# Boden.net
KiCad netlist of a schematic drawn in EAGLE
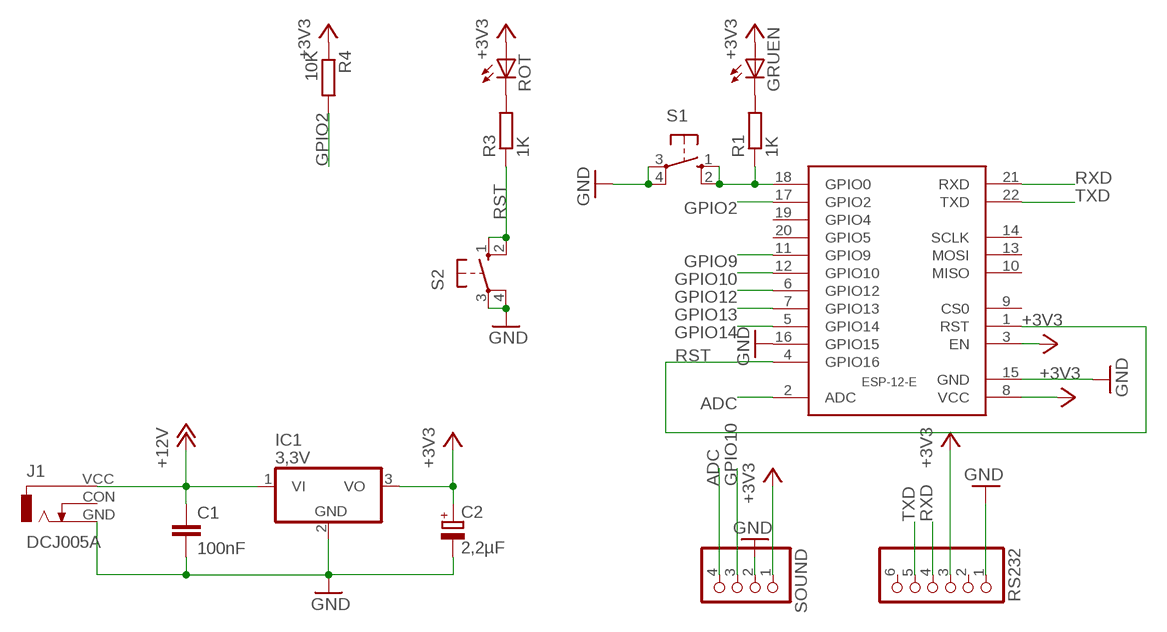
[diagram p0: schematic, sheet 1]

(export (version "E")
  (design (tool "Eeschema 10.0.6"))
  (components
    (comp (ref "C1")
      (value "100nF")
      (footprint "eagle-import:C050-030X075")
      (libsource (lib "eagle-import") (part "C-EU050-030X075"))
    )
    (comp (ref "C2")
      (value "2,2µF")
      (footprint "eagle-import:E2,5-6")
      (libsource (lib "eagle-import") (part "CPOL-EUE2.5-6"))
    )
    (comp (ref "GRUEN")
      (value "LED5MM")
      (footprint "eagle-import:LED5MM")
      (libsource (lib "eagle-import") (part "LED5MM"))
    )
    (comp (ref "IC1")
      (value "3,3V")
      (footprint "eagle-import:TO220V")
      (libsource (lib "eagle-import") (part "78TV05"))
    )
    (comp (ref "J1")
      (value "DCJ005A")
      (footprint "eagle-import:DC005A")
      (libsource (lib "eagle-import") (part "DCJ005A"))
    )
    (comp (ref "R1")
      (value "1K")
      (footprint "eagle-import:0207_10")
      (libsource (lib "eagle-import") (part "R-EU_0207/10"))
    )
    (comp (ref "R3")
      (value "1K")
      (footprint "eagle-import:0207_10")
      (libsource (lib "eagle-import") (part "R-EU_0207/10"))
    )
    (comp (ref "R4")
      (value "10K")
      (footprint "eagle-import:0207_10")
      (libsource (lib "eagle-import") (part "R-EU_0207/10"))
    )
    (comp (ref "ROT")
      (value "LED5MM")
      (footprint "eagle-import:LED5MM")
      (libsource (lib "eagle-import") (part "LED5MM"))
    )
    (comp (ref "RS232")
      (value "PINHD-1X6")
      (footprint "eagle-import:1X06")
      (libsource (lib "eagle-import") (part "PINHD-1X6"))
    )
    (comp (ref "S1")
      (value "10-XX")
      (footprint "eagle-import:B3F-10XX")
      (fields (field (name "MPN") "B3F-1000"))
      (libsource (lib "eagle-import") (part "10-XX"))
    )
    (comp (ref "S2")
      (value "10-XX")
      (footprint "eagle-import:B3F-10XX")
      (fields (field (name "MPN") "B3F-1000"))
      (libsource (lib "eagle-import") (part "10-XX"))
    )
    (comp (ref "SOUND")
      (value "PINHD-1X4")
      (footprint "eagle-import:1X04")
      (libsource (lib "eagle-import") (part "PINHD-1X4"))
    )
    (comp (ref "U$1")
      (value "ESP-12-E")
      (footprint "eagle-import:ESP-12-E")
      (libsource (lib "eagle-import") (part "ESP-12-E"))
    )
  )
  (nets
    (net (code "1") (name "+3V3") (class "Default")
      (node (ref "C2") (pin "+") (pinfunction "+_+") (pintype "passive"))
      (node (ref "GRUEN") (pin "A") (pinfunction "A_A") (pintype "passive"))
      (node (ref "IC1") (pin "3") (pinfunction "VO_3") (pintype "passive"))
      (node (ref "R4") (pin "1") (pinfunction "1_1") (pintype "passive"))
      (node (ref "ROT") (pin "A") (pinfunction "A_A") (pintype "passive"))
      (node (ref "RS232") (pin "3") (pinfunction "3_3") (pintype "passive"))
      (node (ref "SOUND") (pin "1") (pinfunction "1_1") (pintype "passive"))
      (node (ref "U$1") (pin "3") (pinfunction "EN_3") (pintype "bidirectional"))
      (node (ref "U$1") (pin "8") (pinfunction "VCC_8") (pintype "power_in"))
    )
    (net (code "2") (name "+12V") (class "Default")
      (node (ref "C1") (pin "1") (pinfunction "1_1") (pintype "passive"))
      (node (ref "IC1") (pin "1") (pinfunction "VI_1") (pintype "input"))
      (node (ref "J1") (pin "VCC") (pinfunction "1_VCC") (pintype "passive"))
    )
    (net (code "3") (name "/ADC") (class "Default")
      (node (ref "SOUND") (pin "4") (pinfunction "4_4") (pintype "passive"))
      (node (ref "U$1") (pin "2") (pinfunction "ADC_2") (pintype "bidirectional"))
    )
    (net (code "4") (name "/GPIO2") (class "Default")
      (node (ref "R4") (pin "2") (pinfunction "2_2") (pintype "passive"))
      (node (ref "U$1") (pin "17") (pinfunction "GPIO2_17") (pintype "bidirectional"))
    )
    (net (code "5") (name "/GPIO9") (class "Default")
      (node (ref "U$1") (pin "11") (pinfunction "GPIO9_11") (pintype "bidirectional"))
    )
    (net (code "6") (name "/GPIO10") (class "Default")
      (node (ref "SOUND") (pin "3") (pinfunction "3_3") (pintype "passive"))
      (node (ref "U$1") (pin "12") (pinfunction "GPIO10_12") (pintype "bidirectional"))
    )
    (net (code "7") (name "/GPIO12") (class "Default")
      (node (ref "U$1") (pin "6") (pinfunction "GPIO12_6") (pintype "bidirectional"))
    )
    (net (code "8") (name "/GPIO13") (class "Default")
      (node (ref "U$1") (pin "7") (pinfunction "GPIO13_7") (pintype "bidirectional"))
    )
    (net (code "9") (name "/GPIO14") (class "Default")
      (node (ref "U$1") (pin "5") (pinfunction "GPIO14_5") (pintype "bidirectional"))
    )
    (net (code "10") (name "/RST") (class "Default")
      (node (ref "R3") (pin "1") (pinfunction "1_1") (pintype "passive"))
      (node (ref "S2") (pin "1") (pinfunction "S_1") (pintype "passive"))
      (node (ref "S2") (pin "2") (pinfunction "S1_2") (pintype "passive"))
      (node (ref "U$1") (pin "1") (pinfunction "RST_1") (pintype "bidirectional"))
      (node (ref "U$1") (pin "4") (pinfunction "GPIO16_4") (pintype "bidirectional"))
    )
    (net (code "11") (name "/RXD") (class "Default")
      (node (ref "RS232") (pin "4") (pinfunction "4_4") (pintype "passive"))
      (node (ref "U$1") (pin "21") (pinfunction "RXD_21") (pintype "bidirectional"))
    )
    (net (code "12") (name "/TXD") (class "Default")
      (node (ref "RS232") (pin "5") (pinfunction "5_5") (pintype "passive"))
      (node (ref "U$1") (pin "22") (pinfunction "TXD_22") (pintype "bidirectional"))
    )
    (net (code "13") (name "GND") (class "Default")
      (node (ref "C1") (pin "2") (pinfunction "2_2") (pintype "passive"))
      (node (ref "C2") (pin "-") (pinfunction "-_-") (pintype "passive"))
      (node (ref "IC1") (pin "2") (pinfunction "GND_2") (pintype "passive"))
      (node (ref "J1") (pin "GND") (pinfunction "3_GND") (pintype "passive"))
      (node (ref "RS232") (pin "1") (pinfunction "1_1") (pintype "passive"))
      (node (ref "S1") (pin "3") (pinfunction "P_3") (pintype "passive"))
      (node (ref "S1") (pin "4") (pinfunction "P1_4") (pintype "passive"))
      (node (ref "S2") (pin "3") (pinfunction "P_3") (pintype "passive"))
      (node (ref "S2") (pin "4") (pinfunction "P1_4") (pintype "passive"))
      (node (ref "SOUND") (pin "2") (pinfunction "2_2") (pintype "passive"))
      (node (ref "U$1") (pin "15") (pinfunction "GND_15") (pintype "power_in"))
      (node (ref "U$1") (pin "16") (pinfunction "GPIO15_16") (pintype "bidirectional"))
    )
    (net (code "14") (name "Net-(GRUEN-C)") (class "Default")
      (node (ref "GRUEN") (pin "K") (pinfunction "C_K") (pintype "passive"))
      (node (ref "R1") (pin "2") (pinfunction "2_2") (pintype "passive"))
    )
    (net (code "15") (name "Net-(ROT-C)") (class "Default")
      (node (ref "R3") (pin "2") (pinfunction "2_2") (pintype "passive"))
      (node (ref "ROT") (pin "K") (pinfunction "C_K") (pintype "passive"))
    )
    (net (code "16") (name "Net-(S1-S)") (class "Default")
      (node (ref "R1") (pin "1") (pinfunction "1_1") (pintype "passive"))
      (node (ref "S1") (pin "1") (pinfunction "S_1") (pintype "passive"))
      (node (ref "S1") (pin "2") (pinfunction "S1_2") (pintype "passive"))
      (node (ref "U$1") (pin "18") (pinfunction "GPIO0_18") (pintype "bidirectional"))
    )
    (net (code "17") (name "unconnected-(J1-2-PadCON)") (class "Default")
      (node (ref "J1") (pin "CON") (pinfunction "2_CON") (pintype "passive"))
    )
    (net (code "18") (name "unconnected-(RS232-Pad2)") (class "Default")
      (node (ref "RS232") (pin "2") (pinfunction "2_2") (pintype "passive"))
    )
    (net (code "19") (name "unconnected-(RS232-Pad6)") (class "Default")
      (node (ref "RS232") (pin "6") (pinfunction "6_6") (pintype "passive"))
    )
    (net (code "20") (name "unconnected-(U$1-CS0-Pad9)") (class "Default")
      (node (ref "U$1") (pin "9") (pinfunction "CS0_9") (pintype "bidirectional"))
    )
    (net (code "21") (name "unconnected-(U$1-GPIO4-Pad19)") (class "Default")
      (node (ref "U$1") (pin "19") (pinfunction "GPIO4_19") (pintype "bidirectional"))
    )
    (net (code "22") (name "unconnected-(U$1-GPIO5-Pad20)") (class "Default")
      (node (ref "U$1") (pin "20") (pinfunction "GPIO5_20") (pintype "bidirectional"))
    )
    (net (code "23") (name "unconnected-(U$1-MISO-Pad10)") (class "Default")
      (node (ref "U$1") (pin "10") (pinfunction "MISO_10") (pintype "bidirectional"))
    )
    (net (code "24") (name "unconnected-(U$1-MOSI-Pad13)") (class "Default")
      (node (ref "U$1") (pin "13") (pinfunction "MOSI_13") (pintype "bidirectional"))
    )
    (net (code "25") (name "unconnected-(U$1-SCLK-Pad14)") (class "Default")
      (node (ref "U$1") (pin "14") (pinfunction "SCLK_14") (pintype "bidirectional"))
    )
  )
)
